# PWM_Controller.net
KiCad netlist of a schematic drawn in Altium Designer
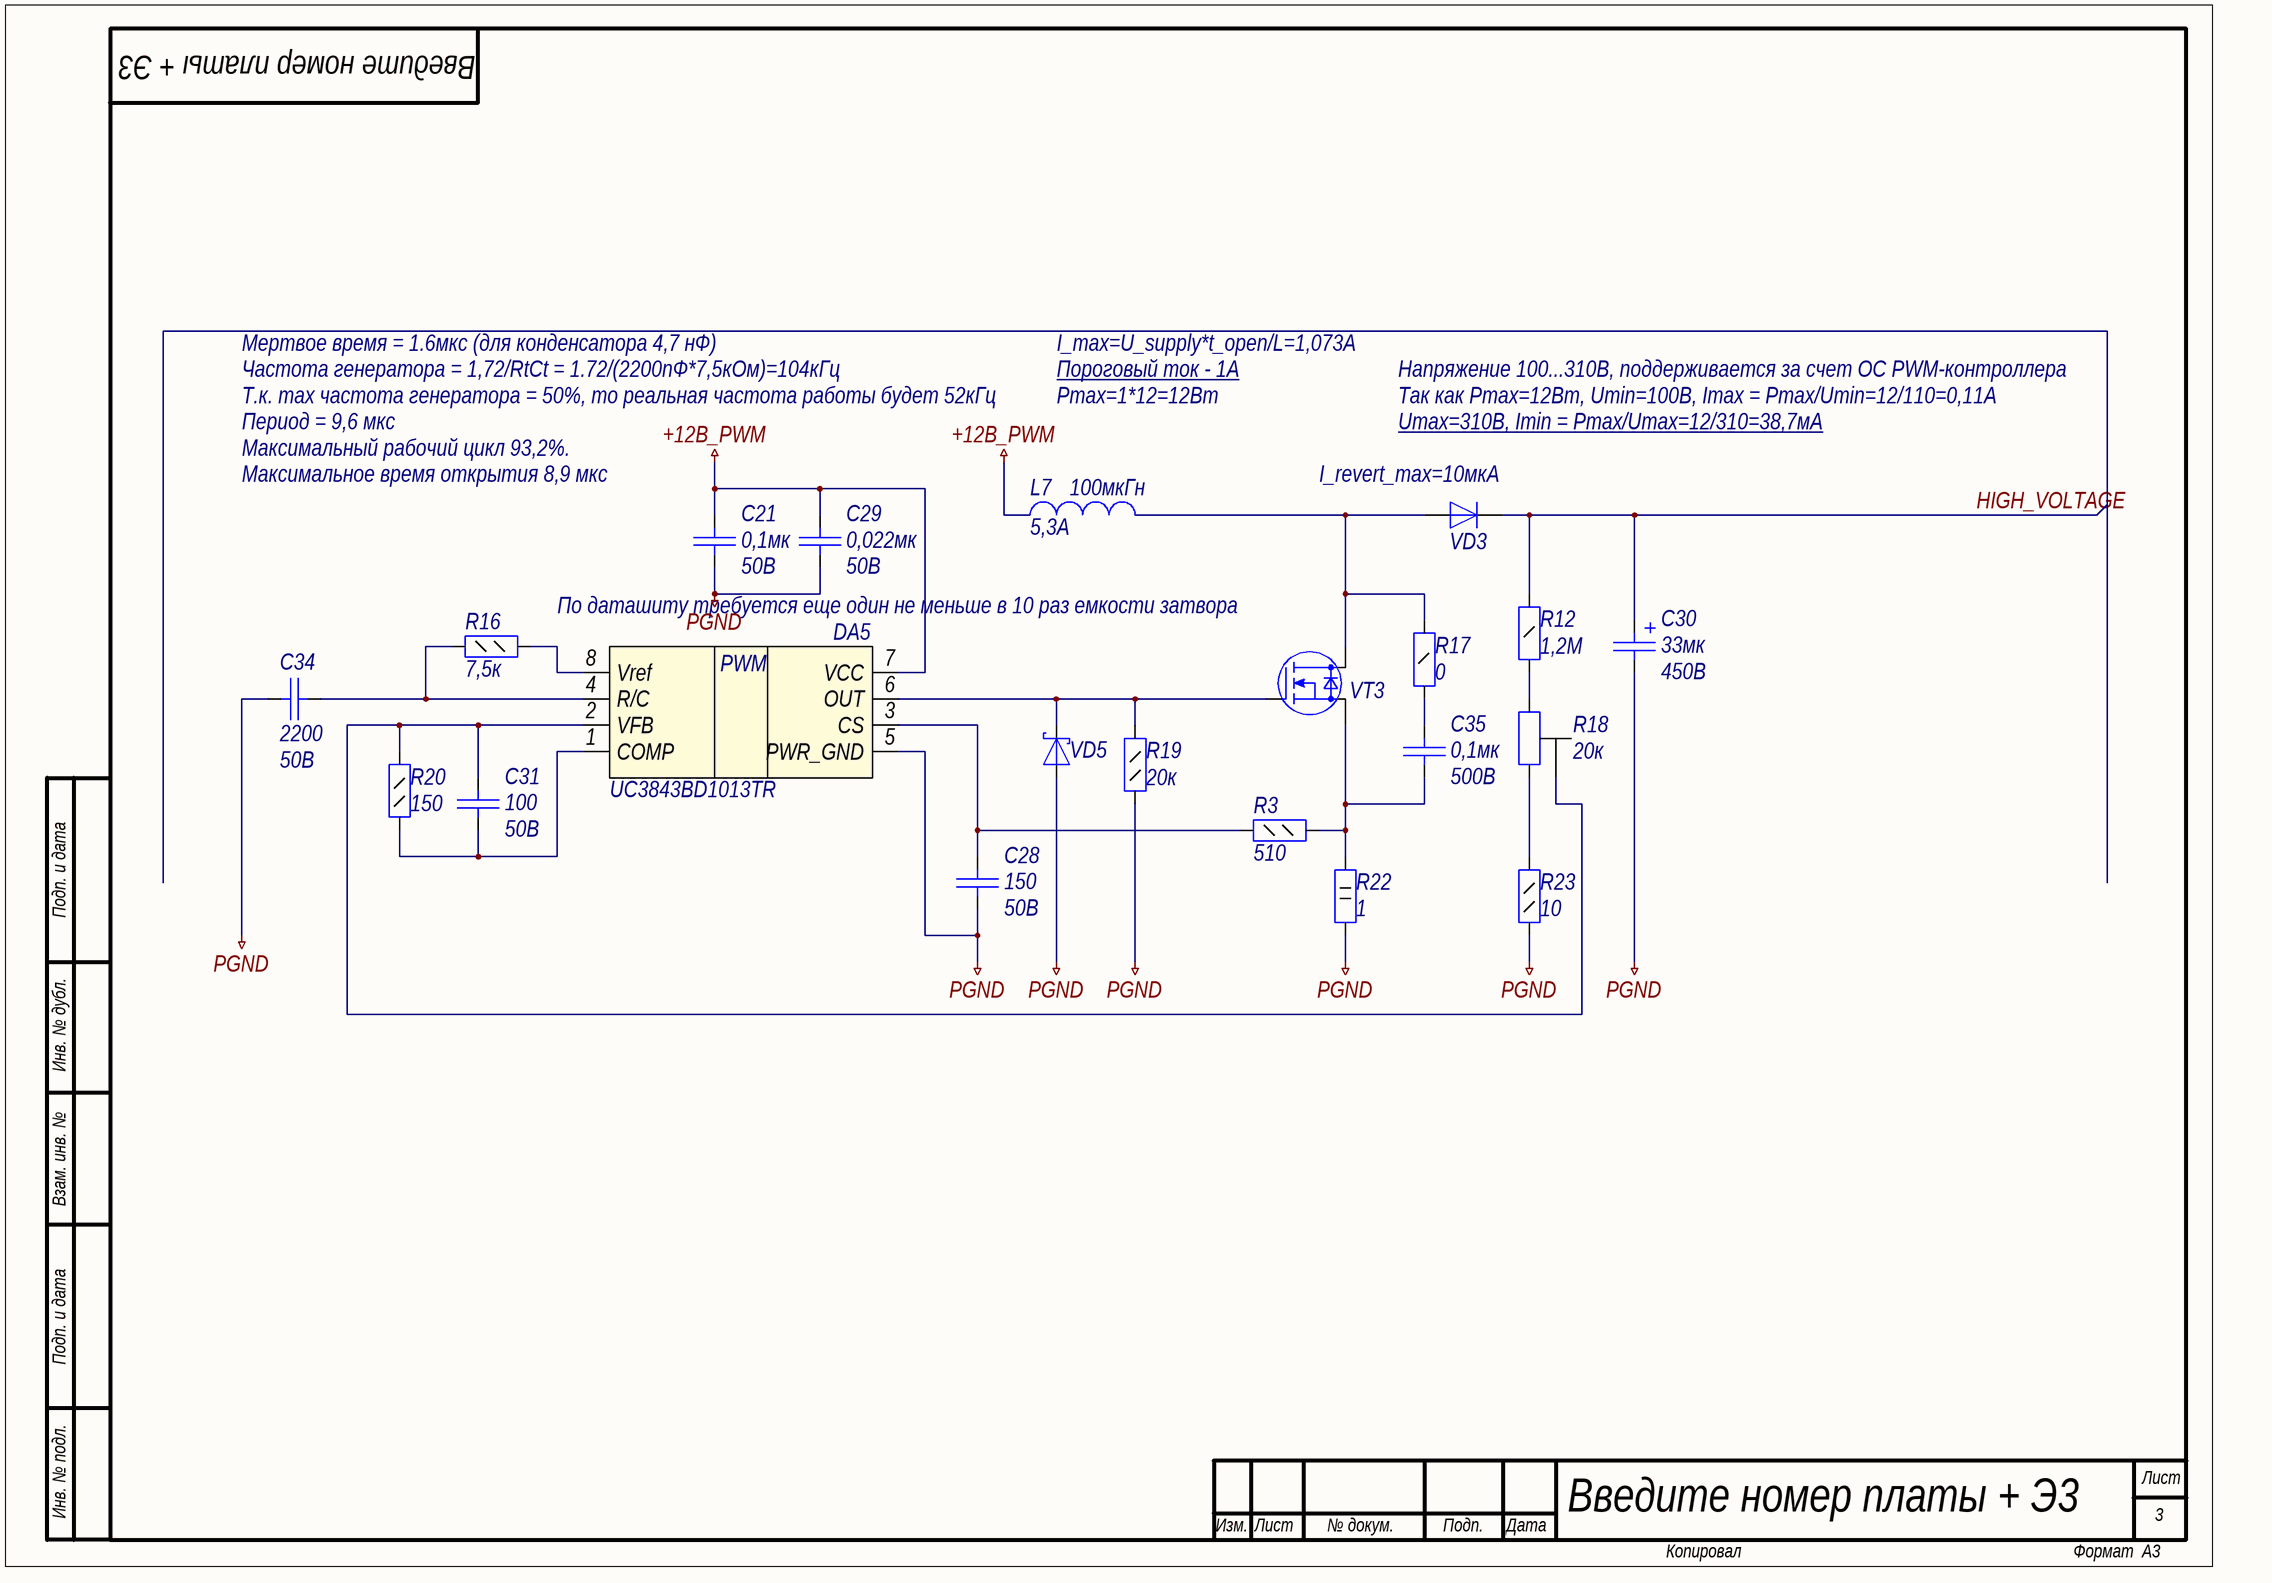
[diagram p0: PWM_Controller.SchDoc]

(export (version "E")
  (design (tool "Eeschema 10.0.6"))
  (components
    (comp (ref "C21")
      (value "0,1мк")
      (footprint "C0805")
      (description "Конденсатор")
      (fields
        (field (name "VOLTAGE") "50В")
        (field (name "PART NUMBER") "GRM21BR71H104KA01L ")
        (field (name "Comment") "Capacitor")
      )
      (libsource (lib "MOP44") (part "Capacitor"))
    )
    (comp (ref "C28")
      (value "150")
      (footprint "C0603")
      (description "Конденсатор")
      (fields
        (field (name "VOLTAGE") "50B")
        (field (name "PART NUMBER") "GRM1885C1H151J")
        (field (name "Comment") "Capacitor")
      )
      (libsource (lib "MOP44") (part "Capacitor"))
    )
    (comp (ref "C29")
      (value "0,022мк")
      (footprint "C1206")
      (description "Конденсатор")
      (fields
        (field (name "VOLTAGE") "50В")
        (field (name "PART NUMBER") "GRM319R71H223K")
        (field (name "Comment") "Capacitor")
      )
      (libsource (lib "MOP44") (part "Capacitor"))
    )
    (comp (ref "C30")
      (value "33мк")
      (footprint "K50-35(16X32)")
      (description "Конденсатор полярный")
      (fields
        (field (name "VOLTAGE") "450В")
        (field (name "PART NUMBER") "ECAP33uF/450V")
        (field (name "Comment") "Capacitor_pol")
      )
      (libsource (lib "MOP44") (part "Capacitor_pol"))
    )
    (comp (ref "C31")
      (value "100")
      (footprint "C0603")
      (description "Конденсатор")
      (fields
        (field (name "VOLTAGE") "50B")
        (field (name "PART NUMBER") "GRM1885C1H101J")
        (field (name "Comment") "Capacitor")
      )
      (libsource (lib "MOP44") (part "Capacitor"))
    )
    (comp (ref "C34")
      (value "2200")
      (footprint "C0805")
      (description "Конденсатор")
      (fields
        (field (name "VOLTAGE") "50В")
        (field (name "PART NUMBER") "GRM216R71H222K")
        (field (name "Comment") "Capacitor")
      )
      (libsource (lib "MOP44") (part "Capacitor"))
    )
    (comp (ref "C35")
      (value "0,1мк")
      (footprint "C1210")
      (description "Конденсатор")
      (fields
        (field (name "VOLTAGE") "500В")
        (field (name "PART NUMBER") "C1210C104KCRACTU")
        (field (name "Comment") "Capacitor")
      )
      (libsource (lib "MOP44") (part "Capacitor"))
    )
    (comp (ref "DA5")
      (value "UC384X")
      (footprint "SO8")
      (description "Current Mode PWM  Controller for Forward and  Flyback Applications")
      (fields (field (name "PART NUMBER") "UC3843BD1013TR"))
      (libsource (lib "MOP44") (part "UC384X"))
    )
    (comp (ref "L7")
      (value "100мкГн")
      (footprint "SRP1770TA")
      (description "EMI Suppression Filter")
      (fields
        (field (name "RATED CURRENT") "5,3A")
        (field (name "PART NUMBER") "SRP1770TA-101M")
        (field (name "Comment") "Inductor")
      )
      (libsource (lib "MOP44") (part "Inductor"))
    )
    (comp (ref "R3")
      (value "510")
      (footprint "R1206")
      (description "Резистор")
      (fields (field (name "PART NUMBER") "RC0805FR-07510RL") (field (name "POWER") "0,125Вт"))
      (libsource (lib "MOP44") (part "Resistor_0,125Вт"))
    )
    (comp (ref "R12")
      (value "1,2М")
      (footprint "R1206")
      (description "Резистор")
      (fields (field (name "PART NUMBER") "RC1206FR-071M2") (field (name "POWER") "0,25Вт"))
      (libsource (lib "MOP44") (part "Resistor_0,25Вт"))
    )
    (comp (ref "R16")
      (value "7,5к")
      (footprint "R0805")
      (description "Резистор")
      (fields (field (name "PART NUMBER") "RC0805FR-077K5") (field (name "POWER") "0,125Вт"))
      (libsource (lib "MOP44") (part "Resistor_0,125Вт"))
    )
    (comp (ref "R17")
      (value "0")
      (footprint "R1206")
      (description "Резистор")
      (fields (field (name "PART NUMBER") "RC1206FR-070RL") (field (name "POWER") "0,25Вт"))
      (libsource (lib "MOP44") (part "Resistor_0,25Вт"))
    )
    (comp (ref "R18")
      (value "20к")
      (footprint "3296Y")
      (description "Potentiometer")
      (fields (field (name "PART NUMBER") "3296Y-1-203LF") (field (name "POWER") "0,5Вт"))
      (libsource (lib "MOP44") (part "Potentiometer"))
    )
    (comp (ref "R19")
      (value "20к")
      (footprint "R0805")
      (description "Резистор")
      (fields (field (name "PART NUMBER") "RC0805FR-0720KL") (field (name "POWER") "0,125Вт"))
      (libsource (lib "") (part "Resistor_0,125Вт_1"))
    )
    (comp (ref "R20")
      (value "150")
      (footprint "R0805")
      (description "Резистор")
      (fields (field (name "PART NUMBER") "RC0805FR-07150RL") (field (name "POWER") "0,125Вт"))
      (libsource (lib "") (part "Resistor_0,125Вт_1"))
    )
    (comp (ref "R22")
      (value "1")
      (footprint "KNP-2")
      (description "Резистор")
      (fields (field (name "PART NUMBER") "KNP-2W-1KJ") (field (name "POWER") "2Вт"))
      (libsource (lib "MOP44") (part "Resistor_2Вт"))
    )
    (comp (ref "R23")
      (value "10")
      (footprint "R0805")
      (description "Резистор")
      (fields (field (name "PART NUMBER") "RC0805FR-0710RL") (field (name "POWER") "0,125Вт"))
      (libsource (lib "") (part "Resistor_0,125Вт_1"))
    )
    (comp (ref "VD3")
      (value "Diode")
      (footprint "SMA")
      (description "Диод")
      (fields (field (name "PART NUMBER") "GS1M"))
      (libsource (lib "MOP44") (part "Diode"))
    )
    (comp (ref "VD5")
      (value "DiodeSchottky")
      (footprint "SOD-123")
      (description "Диод Шоттки")
      (fields (field (name "PART NUMBER") "MBR0520LT1"))
      (libsource (lib "MOP44") (part "DiodeSchottky"))
    )
    (comp (ref "VT3")
      (value "N-MOSFET")
      (footprint "D2PAK")
      (fields (field (name "PART NUMBER") "IRF840ASPBF") (field (name "MANUFACTURER") "Vishay"))
      (libsource (lib "MOP44") (part "N-MOSFET"))
    )
  )
  (nets
    (net (code "1") (name "+12В_PWM") (class "Default")
      (node (ref "C21") (pin "2") (pinfunction "2_2") (pintype "passive"))
      (node (ref "C29") (pin "2") (pinfunction "2_2") (pintype "passive"))
      (node (ref "DA5") (pin "7") (pinfunction "VCC_7") (pintype "passive"))
      (node (ref "L7") (pin "1") (pinfunction "1_1") (pintype "passive"))
    )
    (net (code "2") (name "/HIGH_VOLTAGE") (class "Default")
      (node (ref "C30") (pin "1") (pinfunction "1_1") (pintype "passive"))
      (node (ref "R12") (pin "2") (pinfunction "2_2") (pintype "passive"))
      (node (ref "VD3") (pin "1") (pinfunction "K_1") (pintype "passive"))
    )
    (net (code "3") (name "Net-(C35-Pad2)") (class "Default")
      (node (ref "C35") (pin "2") (pinfunction "2_2") (pintype "passive"))
      (node (ref "R17") (pin "1") (pinfunction "1_1") (pintype "passive"))
    )
    (net (code "4") (name "Net-(DA5-COMP)") (class "Default")
      (node (ref "C31") (pin "1") (pinfunction "1_1") (pintype "passive"))
      (node (ref "DA5") (pin "1") (pinfunction "COMP_1") (pintype "passive"))
      (node (ref "R20") (pin "1") (pinfunction "1_1") (pintype "passive"))
    )
    (net (code "5") (name "Net-(DA5-CS)") (class "Default")
      (node (ref "C28") (pin "2") (pinfunction "2_2") (pintype "passive"))
      (node (ref "DA5") (pin "3") (pinfunction "CS_3") (pintype "passive"))
      (node (ref "R3") (pin "1") (pinfunction "1_1") (pintype "passive"))
    )
    (net (code "6") (name "Net-(DA5-OUT)") (class "Default")
      (node (ref "DA5") (pin "6") (pinfunction "OUT_6") (pintype "passive"))
      (node (ref "R19") (pin "2") (pinfunction "2_2") (pintype "passive"))
      (node (ref "VD5") (pin "1") (pinfunction "K_1") (pintype "passive"))
      (node (ref "VT3") (pin "1") (pinfunction "G_1") (pintype "passive"))
    )
    (net (code "7") (name "Net-(DA5-R{slash}C)") (class "Default")
      (node (ref "C34") (pin "2") (pinfunction "2_2") (pintype "passive"))
      (node (ref "DA5") (pin "4") (pinfunction "R/C_4") (pintype "passive"))
      (node (ref "R16") (pin "1") (pinfunction "1_1") (pintype "passive"))
    )
    (net (code "8") (name "Net-(DA5-VFB)") (class "Default")
      (node (ref "C31") (pin "2") (pinfunction "2_2") (pintype "passive"))
      (node (ref "DA5") (pin "2") (pinfunction "VFB_2") (pintype "passive"))
      (node (ref "R18") (pin "2") (pinfunction "2_2") (pintype "passive"))
      (node (ref "R20") (pin "2") (pinfunction "2_2") (pintype "passive"))
    )
    (net (code "9") (name "Net-(DA5-Vref)") (class "Default")
      (node (ref "DA5") (pin "8") (pinfunction "Vref_8") (pintype "passive"))
      (node (ref "R16") (pin "2") (pinfunction "2_2") (pintype "passive"))
    )
    (net (code "10") (name "Net-(R12-Pad1)") (class "Default")
      (node (ref "R12") (pin "1") (pinfunction "1_1") (pintype "passive"))
      (node (ref "R18") (pin "1") (pinfunction "1_1") (pintype "passive"))
    )
    (net (code "11") (name "Net-(R18-Pad3)") (class "Default")
      (node (ref "R18") (pin "3") (pinfunction "3_3") (pintype "passive"))
      (node (ref "R23") (pin "2") (pinfunction "2_2") (pintype "passive"))
    )
    (net (code "12") (name "Net-(R22-5)") (class "Default")
      (node (ref "C35") (pin "1") (pinfunction "1_1") (pintype "passive"))
      (node (ref "R22") (pin "2") (pinfunction "5_2") (pintype "passive"))
      (node (ref "R3") (pin "2") (pinfunction "2_2") (pintype "passive"))
      (node (ref "VT3") (pin "3") (pinfunction "S_3") (pintype "passive"))
    )
    (net (code "13") (name "Net-(VD3-A)") (class "Default")
      (node (ref "L7") (pin "2") (pinfunction "2_2") (pintype "passive"))
      (node (ref "R17") (pin "2") (pinfunction "2_2") (pintype "passive"))
      (node (ref "VD3") (pin "2") (pinfunction "A_2") (pintype "passive"))
      (node (ref "VT3") (pin "2") (pinfunction "D_2") (pintype "passive"))
    )
    (net (code "14") (name "PGND") (class "Default")
      (node (ref "C21") (pin "1") (pinfunction "1_1") (pintype "passive"))
      (node (ref "C28") (pin "1") (pinfunction "1_1") (pintype "passive"))
      (node (ref "C29") (pin "1") (pinfunction "1_1") (pintype "passive"))
      (node (ref "C30") (pin "2") (pinfunction "2_2") (pintype "passive"))
      (node (ref "C34") (pin "1") (pinfunction "1_1") (pintype "passive"))
      (node (ref "DA5") (pin "5") (pinfunction "PWR_GND_5") (pintype "passive"))
      (node (ref "R19") (pin "1") (pinfunction "1_1") (pintype "passive"))
      (node (ref "R22") (pin "1") (pinfunction "1_1") (pintype "passive"))
      (node (ref "R23") (pin "1") (pinfunction "1_1") (pintype "passive"))
      (node (ref "VD5") (pin "2") (pinfunction "A_2") (pintype "passive"))
    )
  )
)
